# Tiny817_Xplained_Pro_current_measurement.net
KiCad netlist of a schematic drawn in Altium Designer
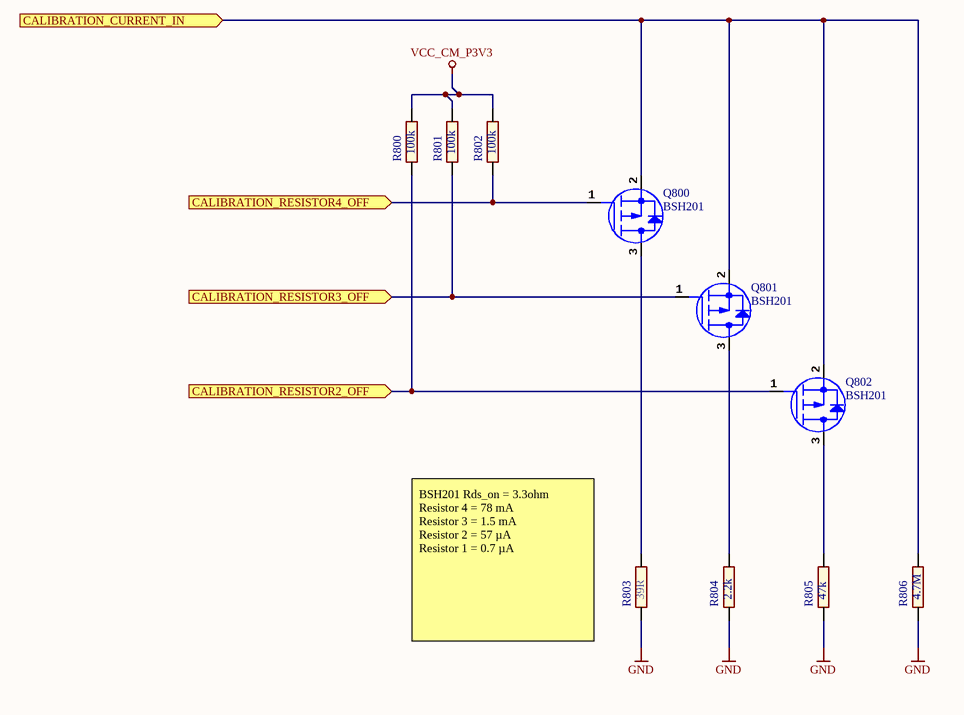
[diagram p0: Tiny817_Xplained_Pro_current_measurement_calibration.SchDoc]

(export (version "E")
  (design (tool "Eeschema 10.0.6"))
  (components
    (comp (ref "Q800")
      (value "BSH201")
      (footprint "AP5-00002")
      (fields (field (name "MANUFACTURER") "NXP") (field (name "MPN") "BSH201,215"))
      (libsource (lib "AltiumDbLib") (part "MOSFET_P_GSD"))
    )
    (comp (ref "Q801")
      (value "BSH201")
      (footprint "AP5-00002")
      (fields (field (name "MANUFACTURER") "NXP") (field (name "MPN") "BSH201,215"))
      (libsource (lib "AltiumDbLib") (part "MOSFET_P_GSD"))
    )
    (comp (ref "Q802")
      (value "BSH201")
      (footprint "AP5-00002")
      (fields (field (name "MANUFACTURER") "NXP") (field (name "MPN") "BSH201,215"))
      (libsource (lib "AltiumDbLib") (part "MOSFET_P_GSD"))
    )
    (comp (ref "R800")
      (value "100k")
      (footprint "AP2-00011")
      (description "Thick film resistor, SMD 0402, 1/16W, 1%")
      (fields (field (name "TOLERANCE") "1 %") (field (name "MANUFACTURER") "ASJ Holdings"))
      (libsource (lib "AltiumDbLib") (part "R2"))
    )
    (comp (ref "R801")
      (value "100k")
      (footprint "AP2-00011")
      (description "Thick film resistor, SMD 0402, 1/16W, 1%")
      (fields (field (name "TOLERANCE") "1 %") (field (name "MANUFACTURER") "ASJ Holdings"))
      (libsource (lib "AltiumDbLib") (part "R2"))
    )
    (comp (ref "R802")
      (value "100k")
      (footprint "AP2-00011")
      (description "Thick film resistor, SMD 0402, 1/16W, 1%")
      (fields (field (name "TOLERANCE") "1 %") (field (name "MANUFACTURER") "ASJ Holdings"))
      (libsource (lib "AltiumDbLib") (part "R2"))
    )
    (comp (ref "R803")
      (value "39R")
      (footprint "AP2-00011")
      (description "Thick film resistor, SMD 0402, 1/16W, 1%")
      (fields (field (name "TOLERANCE") "1 %") (field (name "MANUFACTURER") "ASJ Holdings"))
      (libsource (lib "AltiumDbLib") (part "R2"))
    )
    (comp (ref "R804")
      (value "2.2k")
      (footprint "AP2-00011")
      (description "Thick film resistor, SMD 0402, 1/16W, 1%")
      (fields (field (name "TOLERANCE") "1 %") (field (name "MANUFACTURER") "ASJ Holdings"))
      (libsource (lib "AltiumDbLib") (part "R2"))
    )
    (comp (ref "R805")
      (value "47k")
      (footprint "AP2-00011")
      (description "Thick film resistor, SMD 0402, 1/16W, 1%")
      (fields (field (name "TOLERANCE") "1 %") (field (name "MANUFACTURER") "KOA"))
      (libsource (lib "AltiumDbLib") (part "R2"))
    )
    (comp (ref "R806")
      (value "4.7M")
      (footprint "AP2-00011")
      (description "Thick film SMD 0402 1/16W 1%")
      (fields (field (name "TOLERANCE") "1 %") (field (name "MANUFACTURER") "Yageo"))
      (libsource (lib "AltiumDbLib") (part "R2"))
    )
  )
  (nets
    (net (code "1") (name "/CALIBRATION_CURRENT_IN") (class "Default")
      (node (ref "Q800") (pin "2") (pinfunction "S_2") (pintype "passive"))
      (node (ref "Q801") (pin "2") (pinfunction "S_2") (pintype "passive"))
      (node (ref "Q802") (pin "2") (pinfunction "S_2") (pintype "passive"))
      (node (ref "R806") (pin "2") (pinfunction "2_2") (pintype "passive"))
    )
    (net (code "2") (name "/CALIBRATION_RESISTOR2_OFF") (class "Default")
      (node (ref "Q802") (pin "1") (pinfunction "G_1") (pintype "passive"))
      (node (ref "R800") (pin "1") (pinfunction "1_1") (pintype "passive"))
    )
    (net (code "3") (name "/CALIBRATION_RESISTOR3_OFF") (class "Default")
      (node (ref "Q801") (pin "1") (pinfunction "G_1") (pintype "passive"))
      (node (ref "R801") (pin "1") (pinfunction "1_1") (pintype "passive"))
    )
    (net (code "4") (name "/CALIBRATION_RESISTOR4_OFF") (class "Default")
      (node (ref "Q800") (pin "1") (pinfunction "G_1") (pintype "passive"))
      (node (ref "R802") (pin "1") (pinfunction "1_1") (pintype "passive"))
    )
    (net (code "5") (name "GND") (class "Default")
      (node (ref "R803") (pin "1") (pinfunction "1_1") (pintype "passive"))
      (node (ref "R804") (pin "1") (pinfunction "1_1") (pintype "passive"))
      (node (ref "R805") (pin "1") (pinfunction "1_1") (pintype "passive"))
      (node (ref "R806") (pin "1") (pinfunction "1_1") (pintype "passive"))
    )
    (net (code "6") (name "Net-(Q800-D)") (class "Default")
      (node (ref "Q800") (pin "3") (pinfunction "D_3") (pintype "passive"))
      (node (ref "R803") (pin "2") (pinfunction "2_2") (pintype "passive"))
    )
    (net (code "7") (name "Net-(Q801-D)") (class "Default")
      (node (ref "Q801") (pin "3") (pinfunction "D_3") (pintype "passive"))
      (node (ref "R804") (pin "2") (pinfunction "2_2") (pintype "passive"))
    )
    (net (code "8") (name "Net-(Q802-D)") (class "Default")
      (node (ref "Q802") (pin "3") (pinfunction "D_3") (pintype "passive"))
      (node (ref "R805") (pin "2") (pinfunction "2_2") (pintype "passive"))
    )
    (net (code "9") (name "VCC_CM_P3V3") (class "Default")
      (node (ref "R800") (pin "2") (pinfunction "2_2") (pintype "passive"))
      (node (ref "R801") (pin "2") (pinfunction "2_2") (pintype "passive"))
      (node (ref "R802") (pin "2") (pinfunction "2_2") (pintype "passive"))
    )
  )
)
